# IRIS-EXT-04-BRK_GTX-Breakout.net
KiCad netlist of a schematic drawn in Altium Designer
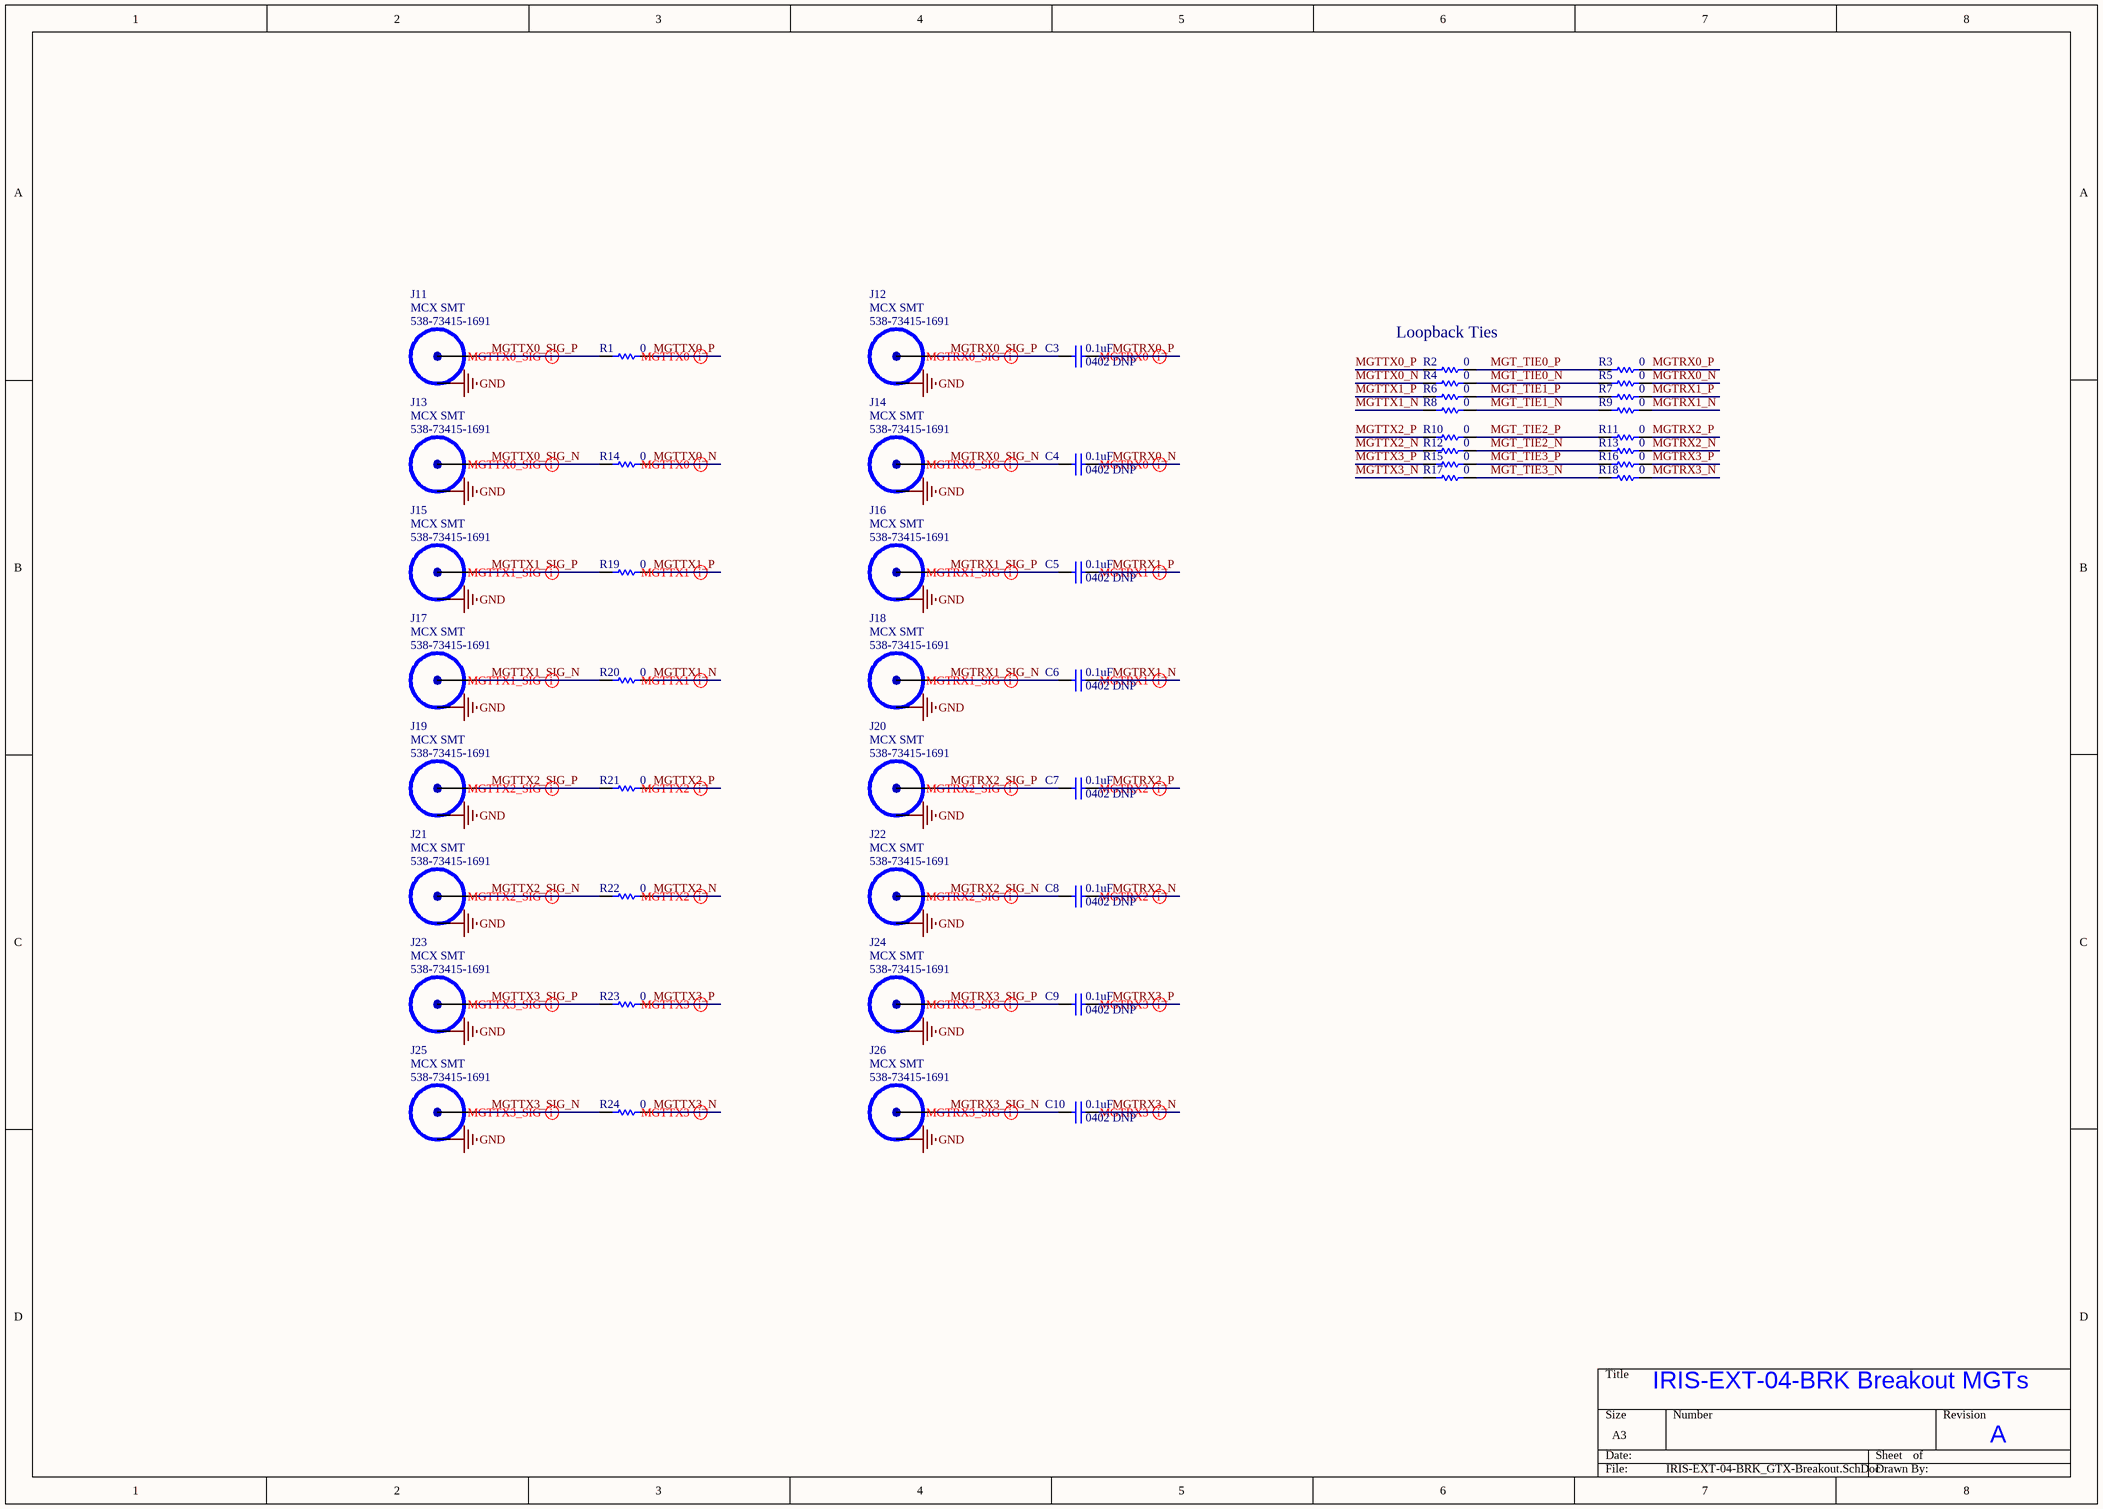
[diagram p0: IRIS-EXT-04-BRK_GTX-Breakout.SchDoc]

(export (version "E")
  (design (tool "Eeschema 10.0.6"))
  (components
    (comp (ref "C3")
      (value "0402 DNP")
      (footprint "0402_SMT_CAP")
      (description "0402 SMT Capacitor")
      (fields (field (name "ALTIUM_VALUE") "0.1uF"))
      (libsource (lib "RNG_Parts") (part "Cap_0402"))
    )
    (comp (ref "C4")
      (value "0402 DNP")
      (footprint "0402_SMT_CAP")
      (description "0402 SMT Capacitor")
      (fields (field (name "ALTIUM_VALUE") "0.1uF"))
      (libsource (lib "RNG_Parts") (part "Cap_0402"))
    )
    (comp (ref "C5")
      (value "0402 DNP")
      (footprint "0402_SMT_CAP")
      (description "0402 SMT Capacitor")
      (fields (field (name "ALTIUM_VALUE") "0.1uF"))
      (libsource (lib "RNG_Parts") (part "Cap_0402"))
    )
    (comp (ref "C6")
      (value "0402 DNP")
      (footprint "0402_SMT_CAP")
      (description "0402 SMT Capacitor")
      (fields (field (name "ALTIUM_VALUE") "0.1uF"))
      (libsource (lib "RNG_Parts") (part "Cap_0402"))
    )
    (comp (ref "C7")
      (value "0402 DNP")
      (footprint "0402_SMT_CAP")
      (description "0402 SMT Capacitor")
      (fields (field (name "ALTIUM_VALUE") "0.1uF"))
      (libsource (lib "RNG_Parts") (part "Cap_0402"))
    )
    (comp (ref "C8")
      (value "0402 DNP")
      (footprint "0402_SMT_CAP")
      (description "0402 SMT Capacitor")
      (fields (field (name "ALTIUM_VALUE") "0.1uF"))
      (libsource (lib "RNG_Parts") (part "Cap_0402"))
    )
    (comp (ref "C9")
      (value "0402 DNP")
      (footprint "0402_SMT_CAP")
      (description "0402 SMT Capacitor")
      (fields (field (name "ALTIUM_VALUE") "0.1uF"))
      (libsource (lib "RNG_Parts") (part "Cap_0402"))
    )
    (comp (ref "C10")
      (value "0402 DNP")
      (footprint "0402_SMT_CAP")
      (description "0402 SMT Capacitor")
      (fields (field (name "ALTIUM_VALUE") "0.1uF"))
      (libsource (lib "RNG_Parts") (part "Cap_0402"))
    )
    (comp (ref "J11")
      (value "MCX SMT")
      (footprint "Molex-734151691")
      (description "Molex 50 Ohm SMT MCX Jack")
      (fields (field (name "SUPPLIER PART NUMBER 1") "538-73415-1691"))
      (libsource (lib "RNG_Parts") (part "Molex-734151691"))
    )
    (comp (ref "J12")
      (value "MCX SMT")
      (footprint "Molex-734151691")
      (description "Molex 50 Ohm SMT MCX Jack")
      (fields (field (name "SUPPLIER PART NUMBER 1") "538-73415-1691"))
      (libsource (lib "RNG_Parts") (part "Molex-734151691"))
    )
    (comp (ref "J13")
      (value "MCX SMT")
      (footprint "Molex-734151691")
      (description "Molex 50 Ohm SMT MCX Jack")
      (fields (field (name "SUPPLIER PART NUMBER 1") "538-73415-1691"))
      (libsource (lib "RNG_Parts") (part "Molex-734151691"))
    )
    (comp (ref "J14")
      (value "MCX SMT")
      (footprint "Molex-734151691")
      (description "Molex 50 Ohm SMT MCX Jack")
      (fields (field (name "SUPPLIER PART NUMBER 1") "538-73415-1691"))
      (libsource (lib "RNG_Parts") (part "Molex-734151691"))
    )
    (comp (ref "J15")
      (value "MCX SMT")
      (footprint "Molex-734151691")
      (description "Molex 50 Ohm SMT MCX Jack")
      (fields (field (name "SUPPLIER PART NUMBER 1") "538-73415-1691"))
      (libsource (lib "RNG_Parts") (part "Molex-734151691"))
    )
    (comp (ref "J16")
      (value "MCX SMT")
      (footprint "Molex-734151691")
      (description "Molex 50 Ohm SMT MCX Jack")
      (fields (field (name "SUPPLIER PART NUMBER 1") "538-73415-1691"))
      (libsource (lib "RNG_Parts") (part "Molex-734151691"))
    )
    (comp (ref "J17")
      (value "MCX SMT")
      (footprint "Molex-734151691")
      (description "Molex 50 Ohm SMT MCX Jack")
      (fields (field (name "SUPPLIER PART NUMBER 1") "538-73415-1691"))
      (libsource (lib "RNG_Parts") (part "Molex-734151691"))
    )
    (comp (ref "J18")
      (value "MCX SMT")
      (footprint "Molex-734151691")
      (description "Molex 50 Ohm SMT MCX Jack")
      (fields (field (name "SUPPLIER PART NUMBER 1") "538-73415-1691"))
      (libsource (lib "RNG_Parts") (part "Molex-734151691"))
    )
    (comp (ref "J19")
      (value "MCX SMT")
      (footprint "Molex-734151691")
      (description "Molex 50 Ohm SMT MCX Jack")
      (fields (field (name "SUPPLIER PART NUMBER 1") "538-73415-1691"))
      (libsource (lib "RNG_Parts") (part "Molex-734151691"))
    )
    (comp (ref "J20")
      (value "MCX SMT")
      (footprint "Molex-734151691")
      (description "Molex 50 Ohm SMT MCX Jack")
      (fields (field (name "SUPPLIER PART NUMBER 1") "538-73415-1691"))
      (libsource (lib "RNG_Parts") (part "Molex-734151691"))
    )
    (comp (ref "J21")
      (value "MCX SMT")
      (footprint "Molex-734151691")
      (description "Molex 50 Ohm SMT MCX Jack")
      (fields (field (name "SUPPLIER PART NUMBER 1") "538-73415-1691"))
      (libsource (lib "RNG_Parts") (part "Molex-734151691"))
    )
    (comp (ref "J22")
      (value "MCX SMT")
      (footprint "Molex-734151691")
      (description "Molex 50 Ohm SMT MCX Jack")
      (fields (field (name "SUPPLIER PART NUMBER 1") "538-73415-1691"))
      (libsource (lib "RNG_Parts") (part "Molex-734151691"))
    )
    (comp (ref "J23")
      (value "MCX SMT")
      (footprint "Molex-734151691")
      (description "Molex 50 Ohm SMT MCX Jack")
      (fields (field (name "SUPPLIER PART NUMBER 1") "538-73415-1691"))
      (libsource (lib "RNG_Parts") (part "Molex-734151691"))
    )
    (comp (ref "J24")
      (value "MCX SMT")
      (footprint "Molex-734151691")
      (description "Molex 50 Ohm SMT MCX Jack")
      (fields (field (name "SUPPLIER PART NUMBER 1") "538-73415-1691"))
      (libsource (lib "RNG_Parts") (part "Molex-734151691"))
    )
    (comp (ref "J25")
      (value "MCX SMT")
      (footprint "Molex-734151691")
      (description "Molex 50 Ohm SMT MCX Jack")
      (fields (field (name "SUPPLIER PART NUMBER 1") "538-73415-1691"))
      (libsource (lib "RNG_Parts") (part "Molex-734151691"))
    )
    (comp (ref "J26")
      (value "MCX SMT")
      (footprint "Molex-734151691")
      (description "Molex 50 Ohm SMT MCX Jack")
      (fields (field (name "SUPPLIER PART NUMBER 1") "538-73415-1691"))
      (libsource (lib "RNG_Parts") (part "Molex-734151691"))
    )
    (comp (ref "R1")
      (value "0")
      (footprint "0402_SMT_RES")
      (description "0402 SMT Resistor")
      (fields (field (name "Comment") "0402 DNP"))
      (libsource (lib "RNG_Parts") (part "Res_0402"))
    )
    (comp (ref "R2")
      (value "0")
      (footprint "0603_SMT_RES")
      (description "0603 SMT Resistor")
      (fields (field (name "Comment") "0603"))
      (libsource (lib "Skylark_Master") (part "Res_0603"))
    )
    (comp (ref "R3")
      (value "0")
      (footprint "0603_SMT_RES")
      (description "0603 SMT Resistor")
      (fields (field (name "Comment") "0603"))
      (libsource (lib "Skylark_Master") (part "Res_0603"))
    )
    (comp (ref "R4")
      (value "0")
      (footprint "0603_SMT_RES")
      (description "0603 SMT Resistor")
      (fields (field (name "Comment") "0603"))
      (libsource (lib "Skylark_Master") (part "Res_0603"))
    )
    (comp (ref "R5")
      (value "0")
      (footprint "0603_SMT_RES")
      (description "0603 SMT Resistor")
      (fields (field (name "Comment") "0603"))
      (libsource (lib "Skylark_Master") (part "Res_0603"))
    )
    (comp (ref "R6")
      (value "0")
      (footprint "0603_SMT_RES")
      (description "0603 SMT Resistor")
      (fields (field (name "Comment") "0603"))
      (libsource (lib "Skylark_Master") (part "Res_0603"))
    )
    (comp (ref "R7")
      (value "0")
      (footprint "0603_SMT_RES")
      (description "0603 SMT Resistor")
      (fields (field (name "Comment") "0603"))
      (libsource (lib "Skylark_Master") (part "Res_0603"))
    )
    (comp (ref "R8")
      (value "0")
      (footprint "0603_SMT_RES")
      (description "0603 SMT Resistor")
      (fields (field (name "Comment") "0603"))
      (libsource (lib "Skylark_Master") (part "Res_0603"))
    )
    (comp (ref "R9")
      (value "0")
      (footprint "0603_SMT_RES")
      (description "0603 SMT Resistor")
      (fields (field (name "Comment") "0603"))
      (libsource (lib "Skylark_Master") (part "Res_0603"))
    )
    (comp (ref "R10")
      (value "0")
      (footprint "0603_SMT_RES")
      (description "0603 SMT Resistor")
      (fields (field (name "Comment") "0603"))
      (libsource (lib "Skylark_Master") (part "Res_0603"))
    )
    (comp (ref "R11")
      (value "0")
      (footprint "0603_SMT_RES")
      (description "0603 SMT Resistor")
      (fields (field (name "Comment") "0603"))
      (libsource (lib "Skylark_Master") (part "Res_0603"))
    )
    (comp (ref "R12")
      (value "0")
      (footprint "0603_SMT_RES")
      (description "0603 SMT Resistor")
      (fields (field (name "Comment") "0603"))
      (libsource (lib "Skylark_Master") (part "Res_0603"))
    )
    (comp (ref "R13")
      (value "0")
      (footprint "0603_SMT_RES")
      (description "0603 SMT Resistor")
      (fields (field (name "Comment") "0603"))
      (libsource (lib "Skylark_Master") (part "Res_0603"))
    )
    (comp (ref "R14")
      (value "0")
      (footprint "0402_SMT_RES")
      (description "0402 SMT Resistor")
      (fields (field (name "Comment") "0402 DNP"))
      (libsource (lib "RNG_Parts") (part "Res_0402"))
    )
    (comp (ref "R15")
      (value "0")
      (footprint "0603_SMT_RES")
      (description "0603 SMT Resistor")
      (fields (field (name "Comment") "0603"))
      (libsource (lib "Skylark_Master") (part "Res_0603"))
    )
    (comp (ref "R16")
      (value "0")
      (footprint "0603_SMT_RES")
      (description "0603 SMT Resistor")
      (fields (field (name "Comment") "0603"))
      (libsource (lib "Skylark_Master") (part "Res_0603"))
    )
    (comp (ref "R17")
      (value "0")
      (footprint "0603_SMT_RES")
      (description "0603 SMT Resistor")
      (fields (field (name "Comment") "0603"))
      (libsource (lib "Skylark_Master") (part "Res_0603"))
    )
    (comp (ref "R18")
      (value "0")
      (footprint "0603_SMT_RES")
      (description "0603 SMT Resistor")
      (fields (field (name "Comment") "0603"))
      (libsource (lib "Skylark_Master") (part "Res_0603"))
    )
    (comp (ref "R19")
      (value "0")
      (footprint "0402_SMT_RES")
      (description "0402 SMT Resistor")
      (fields (field (name "Comment") "0402 DNP"))
      (libsource (lib "RNG_Parts") (part "Res_0402"))
    )
    (comp (ref "R20")
      (value "0")
      (footprint "0402_SMT_RES")
      (description "0402 SMT Resistor")
      (fields (field (name "Comment") "0402 DNP"))
      (libsource (lib "RNG_Parts") (part "Res_0402"))
    )
    (comp (ref "R21")
      (value "0")
      (footprint "0402_SMT_RES")
      (description "0402 SMT Resistor")
      (fields (field (name "Comment") "0402 DNP"))
      (libsource (lib "RNG_Parts") (part "Res_0402"))
    )
    (comp (ref "R22")
      (value "0")
      (footprint "0402_SMT_RES")
      (description "0402 SMT Resistor")
      (fields (field (name "Comment") "0402 DNP"))
      (libsource (lib "RNG_Parts") (part "Res_0402"))
    )
    (comp (ref "R23")
      (value "0")
      (footprint "0402_SMT_RES")
      (description "0402 SMT Resistor")
      (fields (field (name "Comment") "0402 DNP"))
      (libsource (lib "RNG_Parts") (part "Res_0402"))
    )
    (comp (ref "R24")
      (value "0")
      (footprint "0402_SMT_RES")
      (description "0402 SMT Resistor")
      (fields (field (name "Comment") "0402 DNP"))
      (libsource (lib "RNG_Parts") (part "Res_0402"))
    )
  )
  (nets
    (net (code "1") (name "/MGTRX0_N") (class "Default")
      (node (ref "C4") (pin "1") (pinfunction "1_1") (pintype "passive"))
      (node (ref "R5") (pin "1") (pinfunction "1_1") (pintype "passive"))
    )
    (net (code "2") (name "/MGTRX0_P") (class "Default")
      (node (ref "C3") (pin "1") (pinfunction "1_1") (pintype "passive"))
      (node (ref "R3") (pin "1") (pinfunction "1_1") (pintype "passive"))
    )
    (net (code "3") (name "/MGTRX0_SIG_N") (class "Default")
      (node (ref "C4") (pin "2") (pinfunction "2_2") (pintype "passive"))
      (node (ref "J14") (pin "1") (pinfunction "SIG_1") (pintype "power_in"))
    )
    (net (code "4") (name "/MGTRX0_SIG_P") (class "Default")
      (node (ref "C3") (pin "2") (pinfunction "2_2") (pintype "passive"))
      (node (ref "J12") (pin "1") (pinfunction "SIG_1") (pintype "power_in"))
    )
    (net (code "5") (name "/MGTRX1_N") (class "Default")
      (node (ref "C6") (pin "1") (pinfunction "1_1") (pintype "passive"))
      (node (ref "R9") (pin "1") (pinfunction "1_1") (pintype "passive"))
    )
    (net (code "6") (name "/MGTRX1_P") (class "Default")
      (node (ref "C5") (pin "1") (pinfunction "1_1") (pintype "passive"))
      (node (ref "R7") (pin "1") (pinfunction "1_1") (pintype "passive"))
    )
    (net (code "7") (name "/MGTRX1_SIG_N") (class "Default")
      (node (ref "C6") (pin "2") (pinfunction "2_2") (pintype "passive"))
      (node (ref "J18") (pin "1") (pinfunction "SIG_1") (pintype "power_in"))
    )
    (net (code "8") (name "/MGTRX1_SIG_P") (class "Default")
      (node (ref "C5") (pin "2") (pinfunction "2_2") (pintype "passive"))
      (node (ref "J16") (pin "1") (pinfunction "SIG_1") (pintype "power_in"))
    )
    (net (code "9") (name "/MGTRX2_N") (class "Default")
      (node (ref "C8") (pin "1") (pinfunction "1_1") (pintype "passive"))
      (node (ref "R13") (pin "1") (pinfunction "1_1") (pintype "passive"))
    )
    (net (code "10") (name "/MGTRX2_P") (class "Default")
      (node (ref "C7") (pin "1") (pinfunction "1_1") (pintype "passive"))
      (node (ref "R11") (pin "1") (pinfunction "1_1") (pintype "passive"))
    )
    (net (code "11") (name "/MGTRX2_SIG_N") (class "Default")
      (node (ref "C8") (pin "2") (pinfunction "2_2") (pintype "passive"))
      (node (ref "J22") (pin "1") (pinfunction "SIG_1") (pintype "power_in"))
    )
    (net (code "12") (name "/MGTRX2_SIG_P") (class "Default")
      (node (ref "C7") (pin "2") (pinfunction "2_2") (pintype "passive"))
      (node (ref "J20") (pin "1") (pinfunction "SIG_1") (pintype "power_in"))
    )
    (net (code "13") (name "/MGTRX3_N") (class "Default")
      (node (ref "C10") (pin "1") (pinfunction "1_1") (pintype "passive"))
      (node (ref "R18") (pin "1") (pinfunction "1_1") (pintype "passive"))
    )
    (net (code "14") (name "/MGTRX3_P") (class "Default")
      (node (ref "C9") (pin "1") (pinfunction "1_1") (pintype "passive"))
      (node (ref "R16") (pin "1") (pinfunction "1_1") (pintype "passive"))
    )
    (net (code "15") (name "/MGTRX3_SIG_N") (class "Default")
      (node (ref "C10") (pin "2") (pinfunction "2_2") (pintype "passive"))
      (node (ref "J26") (pin "1") (pinfunction "SIG_1") (pintype "power_in"))
    )
    (net (code "16") (name "/MGTRX3_SIG_P") (class "Default")
      (node (ref "C9") (pin "2") (pinfunction "2_2") (pintype "passive"))
      (node (ref "J24") (pin "1") (pinfunction "SIG_1") (pintype "power_in"))
    )
    (net (code "17") (name "/MGTTX0_N") (class "Default")
      (node (ref "R14") (pin "2") (pinfunction "2_2") (pintype "passive"))
      (node (ref "R4") (pin "2") (pinfunction "2_2") (pintype "passive"))
    )
    (net (code "18") (name "/MGTTX0_P") (class "Default")
      (node (ref "R1") (pin "2") (pinfunction "2_2") (pintype "passive"))
      (node (ref "R2") (pin "2") (pinfunction "2_2") (pintype "passive"))
    )
    (net (code "19") (name "/MGTTX0_SIG_N") (class "Default")
      (node (ref "J13") (pin "1") (pinfunction "SIG_1") (pintype "power_in"))
      (node (ref "R14") (pin "1") (pinfunction "1_1") (pintype "passive"))
    )
    (net (code "20") (name "/MGTTX0_SIG_P") (class "Default")
      (node (ref "J11") (pin "1") (pinfunction "SIG_1") (pintype "power_in"))
      (node (ref "R1") (pin "1") (pinfunction "1_1") (pintype "passive"))
    )
    (net (code "21") (name "/MGTTX1_N") (class "Default")
      (node (ref "R20") (pin "2") (pinfunction "2_2") (pintype "passive"))
      (node (ref "R8") (pin "2") (pinfunction "2_2") (pintype "passive"))
    )
    (net (code "22") (name "/MGTTX1_P") (class "Default")
      (node (ref "R19") (pin "2") (pinfunction "2_2") (pintype "passive"))
      (node (ref "R6") (pin "2") (pinfunction "2_2") (pintype "passive"))
    )
    (net (code "23") (name "/MGTTX1_SIG_N") (class "Default")
      (node (ref "J17") (pin "1") (pinfunction "SIG_1") (pintype "power_in"))
      (node (ref "R20") (pin "1") (pinfunction "1_1") (pintype "passive"))
    )
    (net (code "24") (name "/MGTTX1_SIG_P") (class "Default")
      (node (ref "J15") (pin "1") (pinfunction "SIG_1") (pintype "power_in"))
      (node (ref "R19") (pin "1") (pinfunction "1_1") (pintype "passive"))
    )
    (net (code "25") (name "/MGTTX2_N") (class "Default")
      (node (ref "R12") (pin "2") (pinfunction "2_2") (pintype "passive"))
      (node (ref "R22") (pin "2") (pinfunction "2_2") (pintype "passive"))
    )
    (net (code "26") (name "/MGTTX2_P") (class "Default")
      (node (ref "R10") (pin "2") (pinfunction "2_2") (pintype "passive"))
      (node (ref "R21") (pin "2") (pinfunction "2_2") (pintype "passive"))
    )
    (net (code "27") (name "/MGTTX2_SIG_N") (class "Default")
      (node (ref "J21") (pin "1") (pinfunction "SIG_1") (pintype "power_in"))
      (node (ref "R22") (pin "1") (pinfunction "1_1") (pintype "passive"))
    )
    (net (code "28") (name "/MGTTX2_SIG_P") (class "Default")
      (node (ref "J19") (pin "1") (pinfunction "SIG_1") (pintype "power_in"))
      (node (ref "R21") (pin "1") (pinfunction "1_1") (pintype "passive"))
    )
    (net (code "29") (name "/MGTTX3_N") (class "Default")
      (node (ref "R17") (pin "2") (pinfunction "2_2") (pintype "passive"))
      (node (ref "R24") (pin "2") (pinfunction "2_2") (pintype "passive"))
    )
    (net (code "30") (name "/MGTTX3_P") (class "Default")
      (node (ref "R15") (pin "2") (pinfunction "2_2") (pintype "passive"))
      (node (ref "R23") (pin "2") (pinfunction "2_2") (pintype "passive"))
    )
    (net (code "31") (name "/MGTTX3_SIG_N") (class "Default")
      (node (ref "J25") (pin "1") (pinfunction "SIG_1") (pintype "power_in"))
      (node (ref "R24") (pin "1") (pinfunction "1_1") (pintype "passive"))
    )
    (net (code "32") (name "/MGTTX3_SIG_P") (class "Default")
      (node (ref "J23") (pin "1") (pinfunction "SIG_1") (pintype "power_in"))
      (node (ref "R23") (pin "1") (pinfunction "1_1") (pintype "passive"))
    )
    (net (code "33") (name "/MGT_TIE0_N") (class "Default")
      (node (ref "R4") (pin "1") (pinfunction "1_1") (pintype "passive"))
      (node (ref "R5") (pin "2") (pinfunction "2_2") (pintype "passive"))
    )
    (net (code "34") (name "/MGT_TIE0_P") (class "Default")
      (node (ref "R2") (pin "1") (pinfunction "1_1") (pintype "passive"))
      (node (ref "R3") (pin "2") (pinfunction "2_2") (pintype "passive"))
    )
    (net (code "35") (name "/MGT_TIE1_N") (class "Default")
      (node (ref "R8") (pin "1") (pinfunction "1_1") (pintype "passive"))
      (node (ref "R9") (pin "2") (pinfunction "2_2") (pintype "passive"))
    )
    (net (code "36") (name "/MGT_TIE1_P") (class "Default")
      (node (ref "R6") (pin "1") (pinfunction "1_1") (pintype "passive"))
      (node (ref "R7") (pin "2") (pinfunction "2_2") (pintype "passive"))
    )
    (net (code "37") (name "/MGT_TIE2_N") (class "Default")
      (node (ref "R12") (pin "1") (pinfunction "1_1") (pintype "passive"))
      (node (ref "R13") (pin "2") (pinfunction "2_2") (pintype "passive"))
    )
    (net (code "38") (name "/MGT_TIE2_P") (class "Default")
      (node (ref "R10") (pin "1") (pinfunction "1_1") (pintype "passive"))
      (node (ref "R11") (pin "2") (pinfunction "2_2") (pintype "passive"))
    )
    (net (code "39") (name "/MGT_TIE3_N") (class "Default")
      (node (ref "R17") (pin "1") (pinfunction "1_1") (pintype "passive"))
      (node (ref "R18") (pin "2") (pinfunction "2_2") (pintype "passive"))
    )
    (net (code "40") (name "/MGT_TIE3_P") (class "Default")
      (node (ref "R15") (pin "1") (pinfunction "1_1") (pintype "passive"))
      (node (ref "R16") (pin "2") (pinfunction "2_2") (pintype "passive"))
    )
    (net (code "41") (name "GND") (class "Default")
      (node (ref "J11") (pin "0") (pinfunction "GND_0") (pintype "power_in"))
      (node (ref "J12") (pin "0") (pinfunction "GND_0") (pintype "power_in"))
      (node (ref "J13") (pin "0") (pinfunction "GND_0") (pintype "power_in"))
      (node (ref "J14") (pin "0") (pinfunction "GND_0") (pintype "power_in"))
      (node (ref "J15") (pin "0") (pinfunction "GND_0") (pintype "power_in"))
      (node (ref "J16") (pin "0") (pinfunction "GND_0") (pintype "power_in"))
      (node (ref "J17") (pin "0") (pinfunction "GND_0") (pintype "power_in"))
      (node (ref "J18") (pin "0") (pinfunction "GND_0") (pintype "power_in"))
      (node (ref "J19") (pin "0") (pinfunction "GND_0") (pintype "power_in"))
      (node (ref "J20") (pin "0") (pinfunction "GND_0") (pintype "power_in"))
      (node (ref "J21") (pin "0") (pinfunction "GND_0") (pintype "power_in"))
      (node (ref "J22") (pin "0") (pinfunction "GND_0") (pintype "power_in"))
      (node (ref "J23") (pin "0") (pinfunction "GND_0") (pintype "power_in"))
      (node (ref "J24") (pin "0") (pinfunction "GND_0") (pintype "power_in"))
      (node (ref "J25") (pin "0") (pinfunction "GND_0") (pintype "power_in"))
      (node (ref "J26") (pin "0") (pinfunction "GND_0") (pintype "power_in"))
    )
  )
)
